# Main.net
KiCad netlist of a schematic drawn in Altium Designer
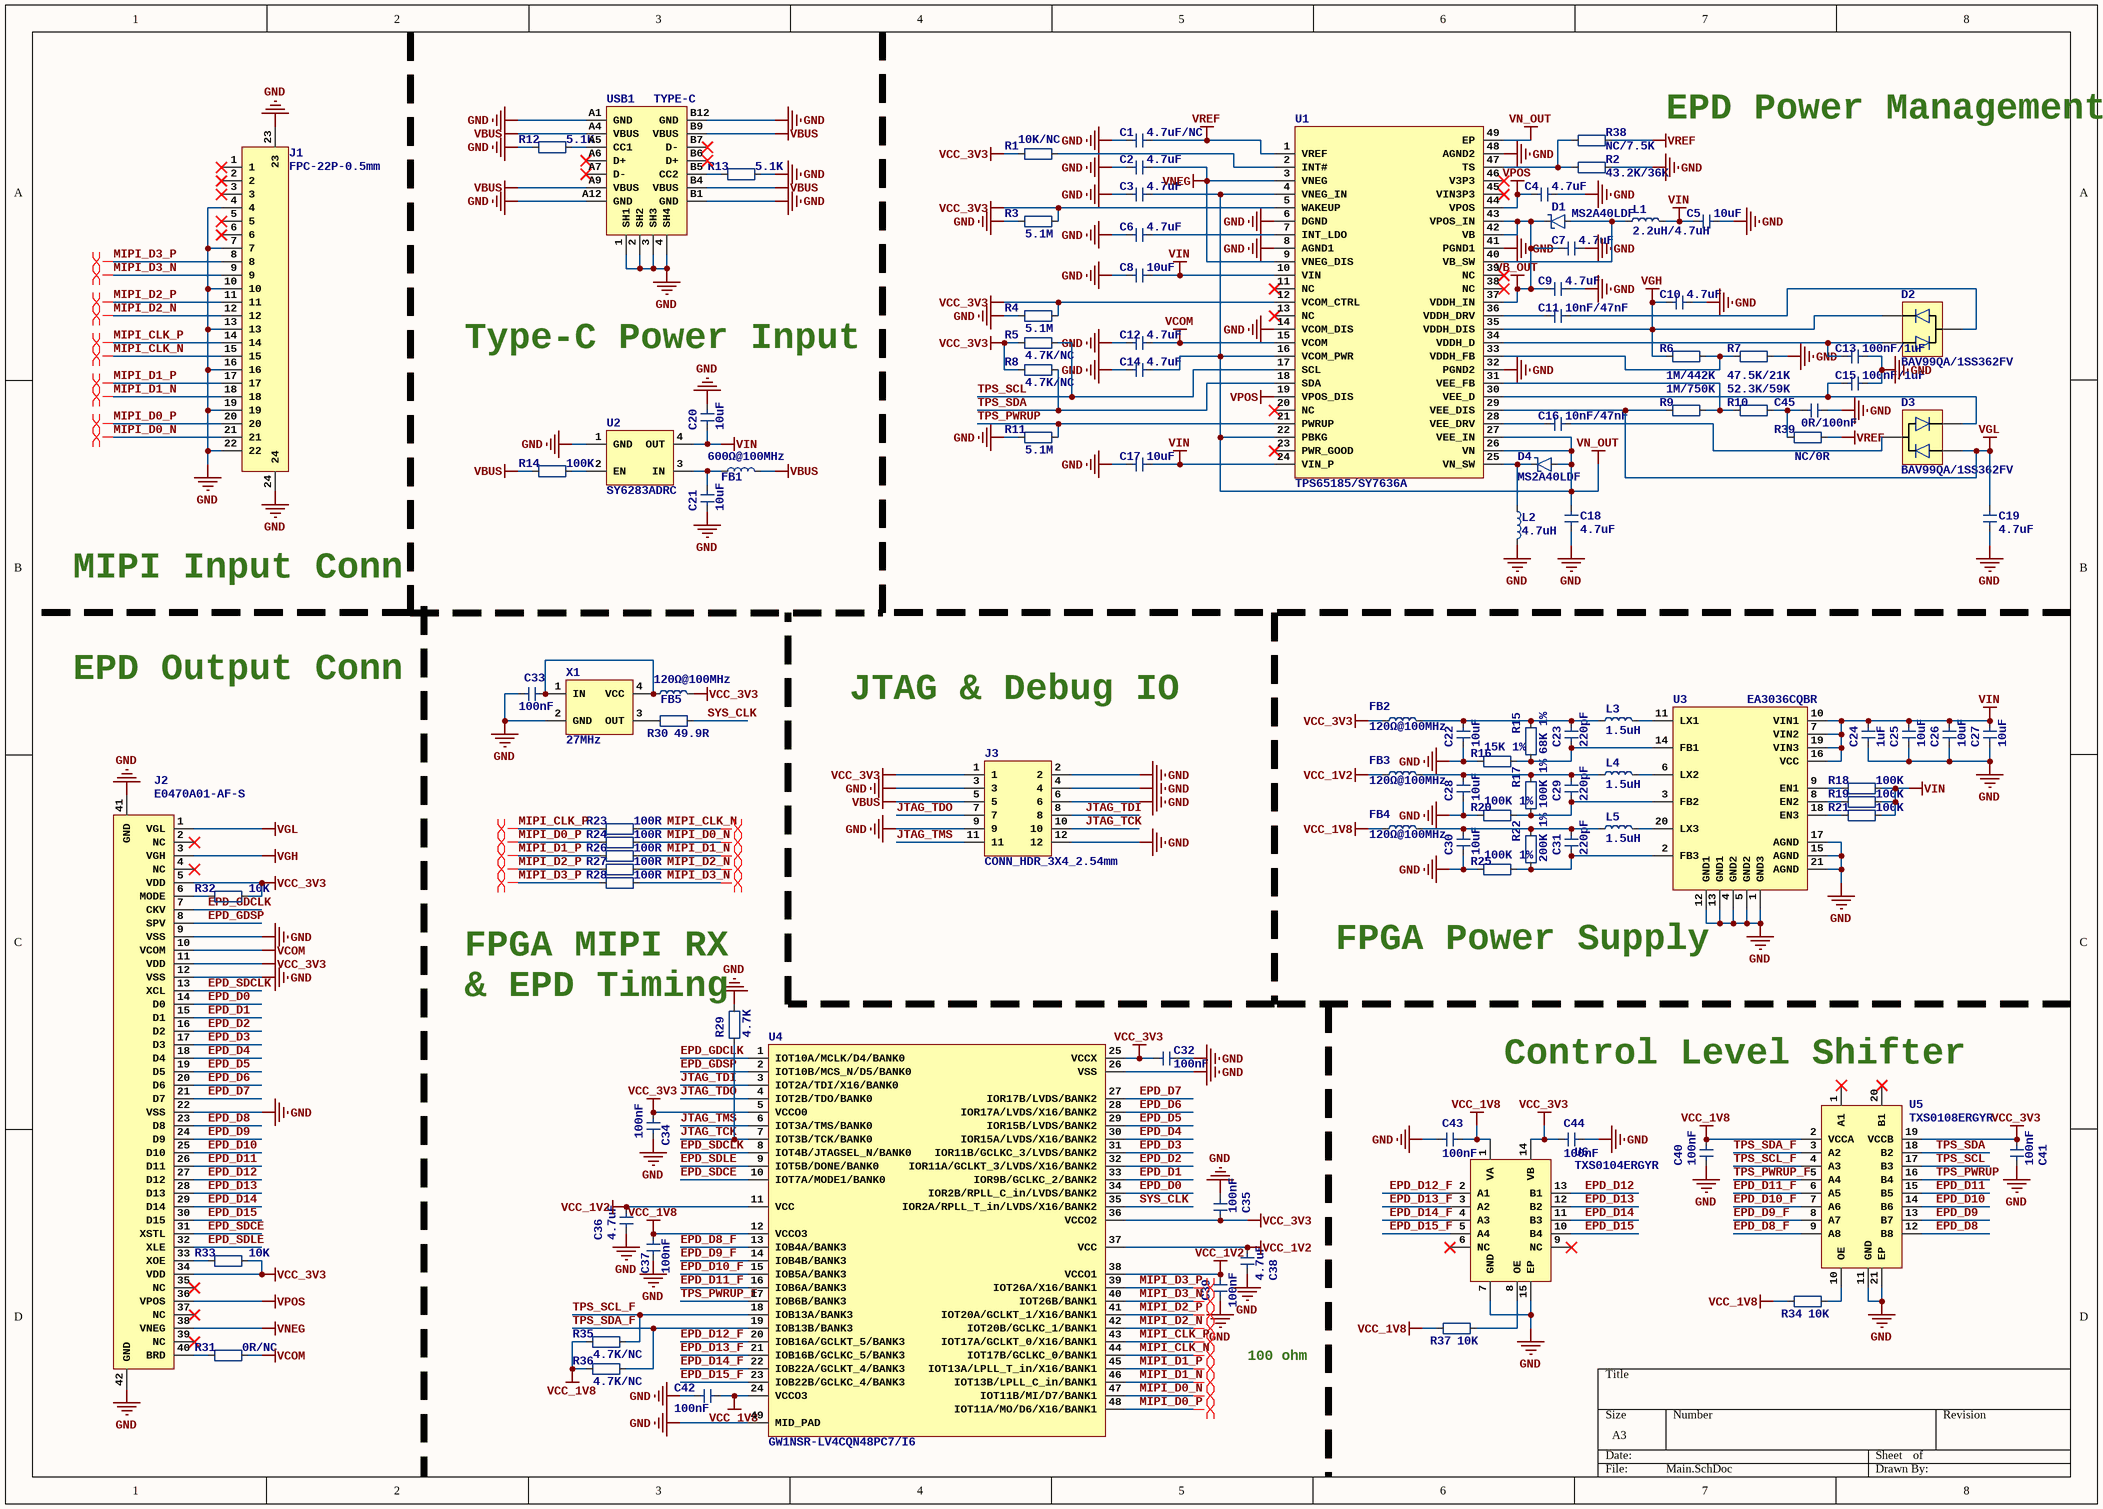
[diagram p0: Main.SchDoc]

(export (version "E")
  (design (tool "Eeschema 10.0.6"))
  (components
    (comp (ref "C1")
      (value "4.7uF/NC")
      (footprint "Capacitor-0402")
      (description "CL05A475MO5NUNC")
      (libsource (lib "mLib") (part "Capacitor-0402"))
    )
    (comp (ref "C2")
      (value "4.7uF")
      (footprint "Capacitor-0805")
      (description "CL21A475KBQNNNE")
      (libsource (lib "mLib") (part "Capacitor-0805"))
    )
    (comp (ref "C3")
      (value "4.7uF")
      (footprint "Capacitor-0805")
      (description "CL21A475KBQNNNE")
      (libsource (lib "mLib") (part "Capacitor-0805"))
    )
    (comp (ref "C4")
      (value "4.7uF")
      (footprint "Capacitor-0805")
      (description "CL21A475KBQNNNE")
      (libsource (lib "mLib") (part "Capacitor-0805"))
    )
    (comp (ref "C5")
      (value "10uF")
      (footprint "Capacitor-0603")
      (description "CL10A106KP8NNNC")
      (libsource (lib "mLib") (part "Capacitor-0603"))
    )
    (comp (ref "C6")
      (value "4.7uF")
      (footprint "Capacitor-0402")
      (description "CL05A475MO5NUNC")
      (libsource (lib "mLib") (part "Capacitor-0402"))
    )
    (comp (ref "C7")
      (value "4.7uF")
      (footprint "Capacitor-0805")
      (description "CL21A475KBQNNNE")
      (libsource (lib "mLib") (part "Capacitor-0805"))
    )
    (comp (ref "C8")
      (value "10uF")
      (footprint "Capacitor-0603")
      (description "CL10A106KP8NNNC")
      (libsource (lib "mLib") (part "Capacitor-0603"))
    )
    (comp (ref "C9")
      (value "4.7uF")
      (footprint "Capacitor-0805")
      (description "CL21A475KBQNNNE")
      (libsource (lib "mLib") (part "Capacitor-0805"))
    )
    (comp (ref "C10")
      (value "4.7uF")
      (footprint "Capacitor-0805")
      (description "CL21A475KBQNNNE")
      (libsource (lib "mLib") (part "Capacitor-0805"))
    )
    (comp (ref "C11")
      (value "10nF/47nF")
      (footprint "Capacitor-0402")
      (description "CL05B103KB5NNNC/CC0402KRX7R9BB473")
      (libsource (lib "mLib") (part "Capacitor-0402"))
    )
    (comp (ref "C12")
      (value "4.7uF")
      (footprint "Capacitor-0402")
      (description "CL05A475MO5NUNC")
      (libsource (lib "mLib") (part "Capacitor-0402"))
    )
    (comp (ref "C13")
      (value "100nF/1uF")
      (footprint "Capacitor-0402")
      (description "0402B104K500NT/HGC0402R5105K500NTEJ")
      (libsource (lib "mLib") (part "Capacitor-0402"))
    )
    (comp (ref "C14")
      (value "4.7uF")
      (footprint "Capacitor-0805")
      (description "CL21A475KBQNNNE")
      (libsource (lib "mLib") (part "Capacitor-0805"))
    )
    (comp (ref "C15")
      (value "100nF/1uF")
      (footprint "Capacitor-0402")
      (description "0402B104K500NT/HGC0402R5105K500NTEJ")
      (libsource (lib "mLib") (part "Capacitor-0402"))
    )
    (comp (ref "C16")
      (value "10nF/47nF")
      (footprint "Capacitor-0402")
      (description "CL05B103KB5NNNC/CC0402KRX7R9BB473")
      (libsource (lib "mLib") (part "Capacitor-0402"))
    )
    (comp (ref "C17")
      (value "10uF")
      (footprint "Capacitor-0603")
      (description "CL10A106KP8NNNC")
      (libsource (lib "mLib") (part "Capacitor-0603"))
    )
    (comp (ref "C18")
      (value "4.7uF")
      (footprint "Capacitor-0805")
      (description "CL21A475KBQNNNE")
      (libsource (lib "mLib") (part "Capacitor-0805"))
    )
    (comp (ref "C19")
      (value "4.7uF")
      (footprint "Capacitor-0805")
      (description "CL21A475KBQNNNE")
      (libsource (lib "mLib") (part "Capacitor-0805"))
    )
    (comp (ref "C20")
      (value "10uF")
      (footprint "Capacitor-0402")
      (description "HGC0402R5106M100NTEJ")
      (libsource (lib "mLib") (part "Capacitor-0402"))
    )
    (comp (ref "C21")
      (value "10uF")
      (footprint "Capacitor-0402")
      (description "HGC0402R5106M100NTEJ")
      (libsource (lib "mLib") (part "Capacitor-0402"))
    )
    (comp (ref "C22")
      (value "10uF")
      (footprint "Capacitor-0402")
      (description "HGC0402R5106M100NTEJ")
      (libsource (lib "mLib") (part "Capacitor-0402"))
    )
    (comp (ref "C23")
      (value "220pF")
      (footprint "Capacitor-0402")
      (description "CL05C221JB5NNNC")
      (libsource (lib "mLib") (part "Capacitor-0402"))
    )
    (comp (ref "C24")
      (value "1uF")
      (footprint "Capacitor-0402")
      (description "HGC0402R5105K500NTEJ")
      (libsource (lib "mLib") (part "Capacitor-0402"))
    )
    (comp (ref "C25")
      (value "10uF")
      (footprint "Capacitor-0402")
      (description "HGC0402R5106M100NTEJ")
      (libsource (lib "mLib") (part "Capacitor-0402"))
    )
    (comp (ref "C26")
      (value "10uF")
      (footprint "Capacitor-0402")
      (description "HGC0402R5106M100NTEJ")
      (libsource (lib "mLib") (part "Capacitor-0402"))
    )
    (comp (ref "C27")
      (value "10uF")
      (footprint "Capacitor-0402")
      (description "HGC0402R5106M100NTEJ")
      (libsource (lib "mLib") (part "Capacitor-0402"))
    )
    (comp (ref "C28")
      (value "10uF")
      (footprint "Capacitor-0402")
      (description "HGC0402R5106M100NTEJ")
      (libsource (lib "mLib") (part "Capacitor-0402"))
    )
    (comp (ref "C29")
      (value "220pF")
      (footprint "Capacitor-0402")
      (description "CL05C221JB5NNNC")
      (libsource (lib "mLib") (part "Capacitor-0402"))
    )
    (comp (ref "C30")
      (value "10uF")
      (footprint "Capacitor-0402")
      (description "HGC0402R5106M100NTEJ")
      (libsource (lib "mLib") (part "Capacitor-0402"))
    )
    (comp (ref "C31")
      (value "220pF")
      (footprint "Capacitor-0402")
      (description "CL05C221JB5NNNC")
      (libsource (lib "mLib") (part "Capacitor-0402"))
    )
    (comp (ref "C32")
      (value "100nF")
      (footprint "Capacitor-0402")
      (description "100nF/X5R/25V")
      (libsource (lib "mLib") (part "Capacitor-0402"))
    )
    (comp (ref "C33")
      (value "100nF")
      (footprint "Capacitor-0402")
      (description "100nF/X5R/25V")
      (libsource (lib "mLib") (part "Capacitor-0402"))
    )
    (comp (ref "C34")
      (value "100nF")
      (footprint "Capacitor-0402")
      (description "100nF/X5R/25V")
      (libsource (lib "mLib") (part "Capacitor-0402"))
    )
    (comp (ref "C35")
      (value "100nF")
      (footprint "Capacitor-0402")
      (description "100nF/X5R/25V")
      (libsource (lib "mLib") (part "Capacitor-0402"))
    )
    (comp (ref "C36")
      (value "4.7uF")
      (footprint "Capacitor-0402")
      (description "4.7uF/X5R/10V")
      (libsource (lib "mLib") (part "Capacitor-0402"))
    )
    (comp (ref "C37")
      (value "100nF")
      (footprint "Capacitor-0402")
      (description "100nF/X5R/25V")
      (libsource (lib "mLib") (part "Capacitor-0402"))
    )
    (comp (ref "C38")
      (value "4.7uF")
      (footprint "Capacitor-0402")
      (description "4.7uF/X5R/10V")
      (libsource (lib "mLib") (part "Capacitor-0402"))
    )
    (comp (ref "C39")
      (value "100nF")
      (footprint "Capacitor-0402")
      (description "100nF/X5R/25V")
      (libsource (lib "mLib") (part "Capacitor-0402"))
    )
    (comp (ref "C40")
      (value "100nF")
      (footprint "Capacitor-0402")
      (description "100nF/X5R/25V")
      (libsource (lib "mLib") (part "Capacitor-0402"))
    )
    (comp (ref "C41")
      (value "100nF")
      (footprint "Capacitor-0402")
      (description "100nF/X5R/25V")
      (libsource (lib "mLib") (part "Capacitor-0402"))
    )
    (comp (ref "C42")
      (value "100nF")
      (footprint "Capacitor-0402")
      (description "100nF/X5R/25V")
      (libsource (lib "mLib") (part "Capacitor-0402"))
    )
    (comp (ref "C43")
      (value "100nF")
      (footprint "Capacitor-0402")
      (description "100nF/X5R/25V")
      (libsource (lib "mLib") (part "Capacitor-0402"))
    )
    (comp (ref "C44")
      (value "100nF")
      (footprint "Capacitor-0402")
      (description "100nF/X5R/25V")
      (libsource (lib "mLib") (part "Capacitor-0402"))
    )
    (comp (ref "C45")
      (value "0R/100nF")
      (footprint "Capacitor-0402")
      (description "CL05B104KB5NNNC")
      (libsource (lib "mLib") (part "Capacitor-0402"))
    )
    (comp (ref "D1")
      (value "MS2A40LDF")
      (footprint "MS2A40LDF-DFN-2_1.6x1.0mm")
      (description "Schottky Diode-DFN-1610-2")
      (libsource (lib "mLib") (part "MS2A40LDF"))
    )
    (comp (ref "D2")
      (value "BAV99QA/1SS362FV")
      (footprint "BAV99QA-DFN-3_1.1x1.0mm")
      (libsource (lib "") (part "BAV99QA_1"))
    )
    (comp (ref "D3")
      (value "BAV99QA/1SS362FV")
      (footprint "BAV99QA-DFN-3_1.1x1.0mm")
      (libsource (lib "mLib") (part "BAV99QA"))
    )
    (comp (ref "D4")
      (value "MS2A40LDF")
      (footprint "MS2A40LDF-DFN-2_1.6x1.0mm")
      (description "Schottky Diode-DFN-1610-2")
      (libsource (lib "mLib") (part "MS2A40LDF"))
    )
    (comp (ref "FB1")
      (value "600Ω@100MHz")
      (footprint "Ferrite Bead-0603")
      (description "UPZ1608U601-1R3TF")
      (libsource (lib "mLib") (part "Ferrite Bead-0603"))
    )
    (comp (ref "FB2")
      (value "120Ω@100MHz")
      (footprint "Ferrite Bead-0402")
      (description "UPZ1005D121-1R3TF")
      (libsource (lib "mLib") (part "Ferrite Bead-0402"))
    )
    (comp (ref "FB3")
      (value "120Ω@100MHz")
      (footprint "Ferrite Bead-0402")
      (description "UPZ1005D121-1R3TF")
      (libsource (lib "mLib") (part "Ferrite Bead-0402"))
    )
    (comp (ref "FB4")
      (value "120Ω@100MHz")
      (footprint "Ferrite Bead-0402")
      (description "UPZ1005D121-1R3TF")
      (libsource (lib "mLib") (part "Ferrite Bead-0402"))
    )
    (comp (ref "FB5")
      (value "120Ω@100MHz")
      (footprint "Ferrite Bead-0402")
      (description "UPZ1005D121-1R3TF")
      (libsource (lib "mLib") (part "Ferrite Bead-0402"))
    )
    (comp (ref "J1")
      (value "FPC-22P-0.5mm")
      (footprint "HC-FPC-05-10-22RLTAG")
      (description "HC-FPC-05-10-22RLTAG")
      (libsource (lib "mLib") (part "FPC-22P-0.5mm"))
    )
    (comp (ref "J2")
      (value "E0470A01-AF-S")
      (footprint "E0470A01-AF-S")
      (description "AFC01-S40FCA-00")
      (libsource (lib "mLib") (part "E0470A01-AF-S"))
    )
    (comp (ref "J3")
      (value "CONN_HDR_3X4_2.54mm")
      (footprint "CONN_HDR_3X4_2.54mm")
      (libsource (lib "mLib") (part "CONN_HDR_3X4_2.54mm"))
    )
    (comp (ref "L1")
      (value "2.2uH/4.7uH")
      (footprint "Inductor-2016")
      (description "FTC201612S2R2MBCA/FTC201610S4R7MBCA")
      (libsource (lib "mLib") (part "Inductor-2016"))
    )
    (comp (ref "L2")
      (value "4.7uH")
      (footprint "Inductor-2016")
      (description "FTC201610S4R7MBCA")
      (libsource (lib "mLib") (part "Inductor-2016"))
    )
    (comp (ref "L3")
      (value "1.5uH")
      (footprint "Inductor-2016")
      (description "FTC201610S1R5MBCA")
      (libsource (lib "mLib") (part "Inductor-2016"))
    )
    (comp (ref "L4")
      (value "1.5uH")
      (footprint "Inductor-2016")
      (description "FTC201610S1R5MBCA")
      (libsource (lib "mLib") (part "Inductor-2016"))
    )
    (comp (ref "L5")
      (value "1.5uH")
      (footprint "Inductor-2016")
      (description "FTC201610S1R5MBCA")
      (libsource (lib "mLib") (part "Inductor-2016"))
    )
    (comp (ref "R1")
      (value "10K/NC")
      (footprint "Resistor-0402")
      (description "Resistor-0402")
      (libsource (lib "mLib") (part "Resistor-0402"))
    )
    (comp (ref "R2")
      (value "43.2K/36K")
      (footprint "Resistor-0402")
      (description "Resistor-0402")
      (libsource (lib "mLib") (part "Resistor-0402"))
    )
    (comp (ref "R3")
      (value "5.1M")
      (footprint "Resistor-0402")
      (description "Resistor-0402")
      (libsource (lib "mLib") (part "Resistor-0402"))
    )
    (comp (ref "R4")
      (value "5.1M")
      (footprint "Resistor-0402")
      (description "Resistor-0402")
      (libsource (lib "mLib") (part "Resistor-0402"))
    )
    (comp (ref "R5")
      (value "4.7K/NC")
      (footprint "Resistor-0402")
      (description "Resistor-0402")
      (libsource (lib "mLib") (part "Resistor-0402"))
    )
    (comp (ref "R6")
      (value "1M/442K")
      (footprint "Resistor-0402")
      (description "Resistor-0402")
      (libsource (lib "mLib") (part "Resistor-0402"))
    )
    (comp (ref "R7")
      (value "47.5K/21K")
      (footprint "Resistor-0402")
      (description "Resistor-0402")
      (libsource (lib "mLib") (part "Resistor-0402"))
    )
    (comp (ref "R8")
      (value "4.7K/NC")
      (footprint "Resistor-0402")
      (description "Resistor-0402")
      (libsource (lib "mLib") (part "Resistor-0402"))
    )
    (comp (ref "R9")
      (value "1M/750K")
      (footprint "Resistor-0402")
      (description "Resistor-0402")
      (libsource (lib "mLib") (part "Resistor-0402"))
    )
    (comp (ref "R10")
      (value "52.3K/59K")
      (footprint "Resistor-0402")
      (description "Resistor-0402")
      (libsource (lib "mLib") (part "Resistor-0402"))
    )
    (comp (ref "R11")
      (value "5.1M")
      (footprint "Resistor-0402")
      (description "Resistor-0402")
      (libsource (lib "mLib") (part "Resistor-0402"))
    )
    (comp (ref "R12")
      (value "5.1K")
      (footprint "Resistor-0402")
      (description "Resistor-0402")
      (libsource (lib "mLib") (part "Resistor-0402"))
    )
    (comp (ref "R13")
      (value "5.1K")
      (footprint "Resistor-0402")
      (description "Resistor-0402")
      (libsource (lib "mLib") (part "Resistor-0402"))
    )
    (comp (ref "R14")
      (value "100K")
      (footprint "Resistor-0402")
      (description "Resistor-0402")
      (libsource (lib "mLib") (part "Resistor-0402"))
    )
    (comp (ref "R15")
      (value "68K 1%")
      (footprint "Resistor-0402")
      (description "Resistor-0402")
      (libsource (lib "mLib") (part "Resistor-0402"))
    )
    (comp (ref "R16")
      (value "15K 1%")
      (footprint "Resistor-0402")
      (description "Resistor-0402")
      (libsource (lib "mLib") (part "Resistor-0402"))
    )
    (comp (ref "R17")
      (value "100K 1%")
      (footprint "Resistor-0402")
      (description "Resistor-0402")
      (libsource (lib "mLib") (part "Resistor-0402"))
    )
    (comp (ref "R18")
      (value "100K")
      (footprint "Resistor-0402")
      (description "Resistor-0402")
      (libsource (lib "mLib") (part "Resistor-0402"))
    )
    (comp (ref "R19")
      (value "100K")
      (footprint "Resistor-0402")
      (description "Resistor-0402")
      (libsource (lib "mLib") (part "Resistor-0402"))
    )
    (comp (ref "R20")
      (value "100K 1%")
      (footprint "Resistor-0402")
      (description "Resistor-0402")
      (libsource (lib "mLib") (part "Resistor-0402"))
    )
    (comp (ref "R21")
      (value "100K")
      (footprint "Resistor-0402")
      (description "Resistor-0402")
      (libsource (lib "mLib") (part "Resistor-0402"))
    )
    (comp (ref "R22")
      (value "200K 1%")
      (footprint "Resistor-0402")
      (description "Resistor-0402")
      (libsource (lib "mLib") (part "Resistor-0402"))
    )
    (comp (ref "R23")
      (value "100R")
      (footprint "Resistor-0402")
      (description "Resistor-0402")
      (libsource (lib "mLib") (part "Resistor-0402"))
    )
    (comp (ref "R24")
      (value "100R")
      (footprint "Resistor-0402")
      (description "Resistor-0402")
      (libsource (lib "mLib") (part "Resistor-0402"))
    )
    (comp (ref "R25")
      (value "100K 1%")
      (footprint "Resistor-0402")
      (description "Resistor-0402")
      (libsource (lib "mLib") (part "Resistor-0402"))
    )
    (comp (ref "R26")
      (value "100R")
      (footprint "Resistor-0402")
      (description "Resistor-0402")
      (libsource (lib "mLib") (part "Resistor-0402"))
    )
    (comp (ref "R27")
      (value "100R")
      (footprint "Resistor-0402")
      (description "Resistor-0402")
      (libsource (lib "mLib") (part "Resistor-0402"))
    )
    (comp (ref "R28")
      (value "100R")
      (footprint "Resistor-0402")
      (description "Resistor-0402")
      (libsource (lib "mLib") (part "Resistor-0402"))
    )
    (comp (ref "R29")
      (value "4.7K")
      (footprint "Resistor-0402")
      (description "Resistor-0402")
      (libsource (lib "mLib") (part "Resistor-0402"))
    )
    (comp (ref "R30")
      (value "49.9R")
      (footprint "Resistor-0402")
      (description "Resistor-0402")
      (libsource (lib "mLib") (part "Resistor-0402"))
    )
    (comp (ref "R31")
      (value "0R/NC")
      (footprint "Resistor-0402")
      (description "Resistor-0402")
      (libsource (lib "mLib") (part "Resistor-0402"))
    )
    (comp (ref "R32")
      (value "10K")
      (footprint "Resistor-0402")
      (description "Resistor-0402")
      (libsource (lib "mLib") (part "Resistor-0402"))
    )
    (comp (ref "R33")
      (value "10K")
      (footprint "Resistor-0402")
      (description "Resistor-0402")
      (libsource (lib "mLib") (part "Resistor-0402"))
    )
    (comp (ref "R34")
      (value "10K")
      (footprint "Resistor-0402")
      (description "Resistor-0402")
      (libsource (lib "mLib") (part "Resistor-0402"))
    )
    (comp (ref "R35")
      (value "4.7K/NC")
      (footprint "Resistor-0402")
      (description "Resistor-0402")
      (libsource (lib "mLib") (part "Resistor-0402"))
    )
    (comp (ref "R36")
      (value "4.7K/NC")
      (footprint "Resistor-0402")
      (description "Resistor-0402")
      (libsource (lib "mLib") (part "Resistor-0402"))
    )
    (comp (ref "R37")
      (value "10K")
      (footprint "Resistor-0402")
      (description "Resistor-0402")
      (libsource (lib "mLib") (part "Resistor-0402"))
    )
    (comp (ref "R38")
      (value "NC/7.5K")
      (footprint "Resistor-0402")
      (description "Resistor-0402")
      (libsource (lib "mLib") (part "Resistor-0402"))
    )
    (comp (ref "R39")
      (value "NC/0R")
      (footprint "Resistor-0402")
      (description "Resistor-0402")
      (libsource (lib "mLib") (part "Resistor-0402"))
    )
    (comp (ref "U1")
      (value "TPS65185/SY7636A")
      (footprint "TPS65185-VQFN-48_6x6mm")
      (libsource (lib "mLib") (part "TPS65185"))
    )
    (comp (ref "U2")
      (value "SY6283ADRC")
      (footprint "SY6283ADRC-dfn-4_1.2x1.6mm")
      (libsource (lib "mLib") (part "SY6283ADRC"))
    )
    (comp (ref "U3")
      (value "EA3036CQBR")
      (footprint "EA3036-QFN-20")
      (libsource (lib "mLib") (part "EA3036CQBR"))
    )
    (comp (ref "U4")
      (value "GW1NSR-LV4CQN48PC7/I6")
      (footprint "GW1NSR-LV4CQN48P-QFN-48_6X6")
      (libsource (lib "mLib") (part "GW1NSR-LV4CQN48P"))
    )
    (comp (ref "U5")
      (value "TXS0108ERGYR")
      (footprint "TXS0108E-VQFN-20-3.5x4.5mm")
      (libsource (lib "mLib") (part "TXS0108E"))
    )
    (comp (ref "U6")
      (value "TXS0104ERGYR")
      (footprint "TXS0104E-VQFN-14-3.5x3.5mm")
      (libsource (lib "mLib") (part "TXS0104E"))
    )
    (comp (ref "USB1")
      (value "TYPE-C")
      (footprint "TYPE-C-16P")
      (description "GT-USB-7010ASV")
      (libsource (lib "mLib") (part "TYPE-C"))
    )
    (comp (ref "X1")
      (value "27MHz")
      (footprint "Oscillator-2016")
      (description "OC7EL89CJO-113YLC-27M")
      (libsource (lib "mLib") (part "Oscillator_Source-2016"))
    )
  )
  (nets
    (net (code "1") (name "/EPD_D0") (class "Default")
      (node (ref "J2") (pin "14") (pinfunction "D0_14") (pintype "passive"))
      (node (ref "U4") (pin "34") (pinfunction "IOR2B/RPLL_C_in/LVDS/BANK2_34") (pintype "passive"))
    )
    (net (code "2") (name "/EPD_D1") (class "Default")
      (node (ref "J2") (pin "15") (pinfunction "D1_15") (pintype "passive"))
      (node (ref "U4") (pin "33") (pinfunction "IOR9B/GCLKC_2/BANK2_33") (pintype "passive"))
    )
    (net (code "3") (name "/EPD_D2") (class "Default")
      (node (ref "J2") (pin "16") (pinfunction "D2_16") (pintype "passive"))
      (node (ref "U4") (pin "32") (pinfunction "IOR11A/GCLKT_3/LVDS/X16/BANK2_32") (pintype "passive"))
    )
    (net (code "4") (name "/EPD_D3") (class "Default")
      (node (ref "J2") (pin "17") (pinfunction "D3_17") (pintype "passive"))
      (node (ref "U4") (pin "31") (pinfunction "IOR11B/GCLKC_3/LVDS/BANK2_31") (pintype "passive"))
    )
    (net (code "5") (name "/EPD_D4") (class "Default")
      (node (ref "J2") (pin "18") (pinfunction "D4_18") (pintype "passive"))
      (node (ref "U4") (pin "30") (pinfunction "IOR15A/LVDS/X16/BANK2_30") (pintype "passive"))
    )
    (net (code "6") (name "/EPD_D5") (class "Default")
      (node (ref "J2") (pin "19") (pinfunction "D5_19") (pintype "passive"))
      (node (ref "U4") (pin "29") (pinfunction "IOR15B/LVDS/BANK2_29") (pintype "passive"))
    )
    (net (code "7") (name "/EPD_D6") (class "Default")
      (node (ref "J2") (pin "20") (pinfunction "D6_20") (pintype "passive"))
      (node (ref "U4") (pin "28") (pinfunction "IOR17A/LVDS/X16/BANK2_28") (pintype "passive"))
    )
    (net (code "8") (name "/EPD_D7") (class "Default")
      (node (ref "J2") (pin "21") (pinfunction "D7_21") (pintype "passive"))
      (node (ref "U4") (pin "27") (pinfunction "IOR17B/LVDS/BANK2_27") (pintype "passive"))
    )
    (net (code "9") (name "/EPD_D8") (class "Default")
      (node (ref "J2") (pin "23") (pinfunction "D8_23") (pintype "passive"))
      (node (ref "U5") (pin "12") (pinfunction "B8_12") (pintype "passive"))
    )
    (net (code "10") (name "/EPD_D8_F") (class "Default")
      (node (ref "U4") (pin "13") (pinfunction "IOB4A/BANK3_13") (pintype "passive"))
      (node (ref "U5") (pin "9") (pinfunction "A8_9") (pintype "passive"))
    )
    (net (code "11") (name "/EPD_D9") (class "Default")
      (node (ref "J2") (pin "24") (pinfunction "D9_24") (pintype "passive"))
      (node (ref "U5") (pin "13") (pinfunction "B7_13") (pintype "passive"))
    )
    (net (code "12") (name "/EPD_D9_F") (class "Default")
      (node (ref "U4") (pin "14") (pinfunction "IOB4B/BANK3_14") (pintype "passive"))
      (node (ref "U5") (pin "8") (pinfunction "A7_8") (pintype "passive"))
    )
    (net (code "13") (name "/EPD_D10") (class "Default")
      (node (ref "J2") (pin "25") (pinfunction "D10_25") (pintype "passive"))
      (node (ref "U5") (pin "14") (pinfunction "B6_14") (pintype "passive"))
    )
    (net (code "14") (name "/EPD_D10_F") (class "Default")
      (node (ref "U4") (pin "15") (pinfunction "IOB5A/BANK3_15") (pintype "passive"))
      (node (ref "U5") (pin "7") (pinfunction "A6_7") (pintype "passive"))
    )
    (net (code "15") (name "/EPD_D11") (class "Default")
      (node (ref "J2") (pin "26") (pinfunction "D11_26") (pintype "passive"))
      (node (ref "U5") (pin "15") (pinfunction "B5_15") (pintype "passive"))
    )
    (net (code "16") (name "/EPD_D11_F") (class "Default")
      (node (ref "U4") (pin "16") (pinfunction "IOB6A/BANK3_16") (pintype "passive"))
      (node (ref "U5") (pin "6") (pinfunction "A5_6") (pintype "passive"))
    )
    (net (code "17") (name "/EPD_D12") (class "Default")
      (node (ref "J2") (pin "27") (pinfunction "D12_27") (pintype "passive"))
      (node (ref "U6") (pin "13") (pinfunction "B1_13") (pintype "passive"))
    )
    (net (code "18") (name "/EPD_D12_F") (class "Default")
      (node (ref "U4") (pin "20") (pinfunction "IOB16A/GCLKT_5/BANK3_20") (pintype "passive"))
      (node (ref "U6") (pin "2") (pinfunction "A1_2") (pintype "passive"))
    )
    (net (code "19") (name "/EPD_D13") (class "Default")
      (node (ref "J2") (pin "28") (pinfunction "D13_28") (pintype "passive"))
      (node (ref "U6") (pin "12") (pinfunction "B2_12") (pintype "passive"))
    )
    (net (code "20") (name "/EPD_D13_F") (class "Default")
      (node (ref "U4") (pin "21") (pinfunction "IOB16B/GCLKC_5/BANK3_21") (pintype "passive"))
      (node (ref "U6") (pin "3") (pinfunction "A2_3") (pintype "passive"))
    )
    (net (code "21") (name "/EPD_D14") (class "Default")
      (node (ref "J2") (pin "29") (pinfunction "D14_29") (pintype "passive"))
      (node (ref "U6") (pin "11") (pinfunction "B3_11") (pintype "passive"))
    )
    (net (code "22") (name "/EPD_D14_F") (class "Default")
      (node (ref "U4") (pin "22") (pinfunction "IOB22A/GCLKT_4/BANK3_22") (pintype "passive"))
      (node (ref "U6") (pin "4") (pinfunction "A3_4") (pintype "passive"))
    )
    (net (code "23") (name "/EPD_D15") (class "Default")
      (node (ref "J2") (pin "30") (pinfunction "D15_30") (pintype "passive"))
      (node (ref "U6") (pin "10") (pinfunction "B4_10") (pintype "passive"))
    )
    (net (code "24") (name "/EPD_D15_F") (class "Default")
      (node (ref "U4") (pin "23") (pinfunction "IOB22B/GCLKC_4/BANK3_23") (pintype "passive"))
      (node (ref "U6") (pin "5") (pinfunction "A4_5") (pintype "passive"))
    )
    (net (code "25") (name "/EPD_GDCLK") (class "Default")
      (node (ref "J2") (pin "7") (pinfunction "CKV_7") (pintype "passive"))
      (node (ref "U4") (pin "1") (pinfunction "IOT10A/MCLK/D4/BANK0_1") (pintype "passive"))
    )
    (net (code "26") (name "/EPD_GDSP") (class "Default")
      (node (ref "J2") (pin "8") (pinfunction "SPV_8") (pintype "passive"))
      (node (ref "U4") (pin "2") (pinfunction "IOT10B/MCS_N/D5/BANK0_2") (pintype "passive"))
    )
    (net (code "27") (name "/EPD_SDCE") (class "Default")
      (node (ref "J2") (pin "31") (pinfunction "XSTL_31") (pintype "passive"))
      (node (ref "U4") (pin "10") (pinfunction "IOT7A/MODE1/BANK0_10") (pintype "passive"))
    )
    (net (code "28") (name "/EPD_SDCLK") (class "Default")
      (node (ref "J2") (pin "13") (pinfunction "XCL_13") (pintype "passive"))
      (node (ref "U4") (pin "8") (pinfunction "IOT4B/JTAGSEL_N/BANK0_8") (pintype "passive"))
    )
    (net (code "29") (name "/EPD_SDLE") (class "Default")
      (node (ref "J2") (pin "32") (pinfunction "XLE_32") (pintype "passive"))
      (node (ref "U4") (pin "9") (pinfunction "IOT5B/DONE/BANK0_9") (pintype "passive"))
    )
    (net (code "30") (name "/JTAG_TCK") (class "Default")
      (node (ref "J3") (pin "10") (pinfunction "10_10") (pintype "passive"))
      (node (ref "R29") (pin "1") (pinfunction "1_1") (pintype "passive"))
      (node (ref "U4") (pin "7") (pinfunction "IOT3B/TCK/BANK0_7") (pintype "passive"))
    )
    (net (code "31") (name "/JTAG_TDI") (class "Default")
      (node (ref "J3") (pin "8") (pinfunction "8_8") (pintype "passive"))
      (node (ref "U4") (pin "3") (pinfunction "IOT2A/TDI/X16/BANK0_3") (pintype "passive"))
    )
    (net (code "32") (name "/JTAG_TDO") (class "Default")
      (node (ref "J3") (pin "7") (pinfunction "7_7") (pintype "passive"))
      (node (ref "U4") (pin "4") (pinfunction "IOT2B/TDO/BANK0_4") (pintype "passive"))
    )
    (net (code "33") (name "/JTAG_TMS") (class "Default")
      (node (ref "J3") (pin "11") (pinfunction "11_11") (pintype "passive"))
      (node (ref "U4") (pin "6") (pinfunction "IOT3A/TMS/BANK0_6") (pintype "passive"))
    )
    (net (code "34") (name "/MIPI_CLK_N") (class "Default")
      (node (ref "J1") (pin "15") (pinfunction "15_15") (pintype "passive"))
      (node (ref "R23") (pin "1") (pinfunction "1_1") (pintype "passive"))
      (node (ref "U4") (pin "44") (pinfunction "IOT17B/GCLKC_0/BANK1_44") (pintype "passive"))
    )
    (net (code "35") (name "/MIPI_CLK_P") (class "Default")
      (node (ref "J1") (pin "14") (pinfunction "14_14") (pintype "passive"))
      (node (ref "R23") (pin "2") (pinfunction "2_2") (pintype "passive"))
      (node (ref "U4") (pin "43") (pinfunction "IOT17A/GCLKT_0/X16/BANK1_43") (pintype "passive"))
    )
    (net (code "36") (name "/MIPI_D0_N") (class "Default")
      (node (ref "J1") (pin "21") (pinfunction "21_21") (pintype "passive"))
      (node (ref "R24") (pin "1") (pinfunction "1_1") (pintype "passive"))
      (node (ref "U4") (pin "47") (pinfunction "IOT11B/MI/D7/BANK1_47") (pintype "passive"))
    )
    (net (code "37") (name "/MIPI_D0_P") (class "Default")
      (node (ref "J1") (pin "20") (pinfunction "20_20") (pintype "passive"))
      (node (ref "R24") (pin "2") (pinfunction "2_2") (pintype "passive"))
      (node (ref "U4") (pin "48") (pinfunction "IOT11A/MO/D6/X16/BANK1_48") (pintype "passive"))
    )
    (net (code "38") (name "/MIPI_D1_N") (class "Default")
      (node (ref "J1") (pin "18") (pinfunction "18_18") (pintype "passive"))
      (node (ref "R26") (pin "1") (pinfunction "1_1") (pintype "passive"))
      (node (ref "U4") (pin "46") (pinfunction "IOT13B/LPLL_C_in/BANK1_46") (pintype "passive"))
    )
    (net (code "39") (name "/MIPI_D1_P") (class "Default")
      (node (ref "J1") (pin "17") (pinfunction "17_17") (pintype "passive"))
      (node (ref "R26") (pin "2") (pinfunction "2_2") (pintype "passive"))
      (node (ref "U4") (pin "45") (pinfunction "IOT13A/LPLL_T_in/X16/BANK1_45") (pintype "passive"))
    )
    (net (code "40") (name "/MIPI_D2_N") (class "Default")
      (node (ref "J1") (pin "12") (pinfunction "12_12") (pintype "passive"))
      (node (ref "R27") (pin "1") (pinfunction "1_1") (pintype "passive"))
      (node (ref "U4") (pin "42") (pinfunction "IOT20B/GCLKC_1/BANK1_42") (pintype "passive"))
    )
    (net (code "41") (name "/MIPI_D2_P") (class "Default")
      (node (ref "J1") (pin "11") (pinfunction "11_11") (pintype "passive"))
      (node (ref "R27") (pin "2") (pinfunction "2_2") (pintype "passive"))
      (node (ref "U4") (pin "41") (pinfunction "IOT20A/GCLKT_1/X16/BANK1_41") (pintype "passive"))
    )
    (net (code "42") (name "/MIPI_D3_N") (class "Default")
      (node (ref "J1") (pin "9") (pinfunction "9_9") (pintype "passive"))
      (node (ref "R28") (pin "1") (pinfunction "1_1") (pintype "passive"))
      (node (ref "U4") (pin "40") (pinfunction "IOT26B/BANK1_40") (pintype "passive"))
    )
    (net (code "43") (name "/MIPI_D3_P") (class "Default")
      (node (ref "J1") (pin "8") (pinfunction "8_8") (pintype "passive"))
      (node (ref "R28") (pin "2") (pinfunction "2_2") (pintype "passive"))
      (node (ref "U4") (pin "39") (pinfunction "IOT26A/X16/BANK1_39") (pintype "passive"))
    )
    (net (code "44") (name "/SYS_CLK") (class "Default")
      (node (ref "R30") (pin "1") (pinfunction "1_1") (pintype "passive"))
      (node (ref "U4") (pin "35") (pinfunction "IOR2A/RPLL_T_in/LVDS/X16/BANK2_35") (pintype "passive"))
    )
    (net (code "45") (name "/TPS_PWRUP") (class "Default")
      (node (ref "R11") (pin "1") (pinfunction "1_1") (pintype "passive"))
      (node (ref "U1") (pin "21") (pinfunction "PWRUP_21") (pintype "passive"))
      (node (ref "U5") (pin "16") (pinfunction "B4_16") (pintype "passive"))
    )
    (net (code "46") (name "/TPS_PWRUP_F") (class "Default")
      (node (ref "U4") (pin "17") (pinfunction "IOB6B/BANK3_17") (pintype "passive"))
      (node (ref "U5") (pin "5") (pinfunction "A4_5") (pintype "passive"))
    )
    (net (code "47") (name "/TPS_SCL") (class "Default")
      (node (ref "R5") (pin "1") (pinfunction "1_1") (pintype "passive"))
      (node (ref "U1") (pin "17") (pinfunction "SCL_17") (pintype "passive"))
      (node (ref "U5") (pin "17") (pinfunction "B3_17") (pintype "passive"))
    )
    (net (code "48") (name "/TPS_SCL_F") (class "Default")
      (node (ref "R35") (pin "1") (pinfunction "1_1") (pintype "passive"))
      (node (ref "U4") (pin "18") (pinfunction "IOB13A/BANK3_18") (pintype "passive"))
      (node (ref "U5") (pin "4") (pinfunction "A3_4") (pintype "passive"))
    )
    (net (code "49") (name "/TPS_SDA") (class "Default")
      (node (ref "R8") (pin "1") (pinfunction "1_1") (pintype "passive"))
      (node (ref "U1") (pin "18") (pinfunction "SDA_18") (pintype "passive"))
      (node (ref "U5") (pin "18") (pinfunction "B2_18") (pintype "passive"))
    )
    (net (code "50") (name "/TPS_SDA_F") (class "Default")
      (node (ref "R36") (pin "1") (pinfunction "1_1") (pintype "passive"))
      (node (ref "U4") (pin "19") (pinfunction "IOB13B/BANK3_19") (pintype "passive"))
      (node (ref "U5") (pin "3") (pinfunction "A2_3") (pintype "passive"))
    )
    (net (code "51") (name "GND") (class "Default")
      (node (ref "C1") (pin "1") (pinfunction "1_1") (pintype "passive"))
      (node (ref "C10") (pin "2") (pinfunction "2_2") (pintype "passive"))
      (node (ref "C12") (pin "1") (pinfunction "1_1") (pintype "passive"))
      (node (ref "C13") (pin "2") (pinfunction "2_2") (pintype "passive"))
      (node (ref "C14") (pin "1") (pinfunction "1_1") (pintype "passive"))
      (node (ref "C15") (pin "2") (pinfunction "2_2") (pintype "passive"))
      (node (ref "C17") (pin "1") (pinfunction "1_1") (pintype "passive"))
      (node (ref "C18") (pin "1") (pinfunction "1_1") (pintype "passive"))
      (node (ref "C19") (pin "1") (pinfunction "1_1") (pintype "passive"))
      (node (ref "C2") (pin "1") (pinfunction "1_1") (pintype "passive"))
      (node (ref "C20") (pin "2") (pinfunction "2_2") (pintype "passive"))
      (node (ref "C21") (pin "1") (pinfunction "1_1") (pintype "passive"))
      (node (ref "C22") (pin "1") (pinfunction "1_1") (pintype "passive"))
      (node (ref "C24") (pin "1") (pinfunction "1_1") (pintype "passive"))
      (node (ref "C25") (pin "1") (pinfunction "1_1") (pintype "passive"))
      (node (ref "C26") (pin "1") (pinfunction "1_1") (pintype "passive"))
      (node (ref "C27") (pin "1") (pinfunction "1_1") (pintype "passive"))
      (node (ref "C28") (pin "1") (pinfunction "1_1") (pintype "passive"))
      (node (ref "C3") (pin "1") (pinfunction "1_1") (pintype "passive"))
      (node (ref "C30") (pin "1") (pinfunction "1_1") (pintype "passive"))
      (node (ref "C32") (pin "2") (pinfunction "2_2") (pintype "passive"))
      (node (ref "C33") (pin "2") (pinfunction "2_2") (pintype "passive"))
      (node (ref "C34") (pin "1") (pinfunction "1_1") (pintype "passive"))
      (node (ref "C35") (pin "2") (pinfunction "2_2") (pintype "passive"))
      (node (ref "C36") (pin "1") (pinfunction "1_1") (pintype "passive"))
      (node (ref "C37") (pin "1") (pinfunction "1_1") (pintype "passive"))
      (node (ref "C38") (pin "1") (pinfunction "1_1") (pintype "passive"))
      (node (ref "C39") (pin "1") (pinfunction "1_1") (pintype "passive"))
      (node (ref "C4") (pin "2") (pinfunction "2_2") (pintype "passive"))
      (node (ref "C40") (pin "1") (pinfunction "1_1") (pintype "passive"))
      (node (ref "C41") (pin "1") (pinfunction "1_1") (pintype "passive"))
      (node (ref "C42") (pin "2") (pinfunction "2_2") (pintype "passive"))
      (node (ref "C43") (pin "2") (pinfunction "2_2") (pintype "passive"))
      (node (ref "C44") (pin "1") (pinfunction "1_1") (pintype "passive"))
      (node (ref "C45") (pin "1") (pinfunction "1_1") (pintype "passive"))
      (node (ref "C5") (pin "2") (pinfunction "2_2") (pintype "passive"))
      (node (ref "C6") (pin "1") (pinfunction "1_1") (pintype "passive"))
      (node (ref "C7") (pin "2") (pinfunction "2_2") (pintype "passive"))
      (node (ref "C8") (pin "1") (pinfunction "1_1") (pintype "passive"))
      (node (ref "C9") (pin "2") (pinfunction "2_2") (pintype "passive"))
      (node (ref "J1") (pin "10") (pinfunction "10_10") (pintype "passive"))
      (node (ref "J1") (pin "13") (pinfunction "13_13") (pintype "passive"))
      (node (ref "J1") (pin "16") (pinfunction "16_16") (pintype "passive"))
      (node (ref "J1") (pin "19") (pinfunction "19_19") (pintype "passive"))
      (node (ref "J1") (pin "22") (pinfunction "22_22") (pintype "passive"))
      (node (ref "J1") (pin "23") (pinfunction "23_23") (pintype "passive"))
      (node (ref "J1") (pin "24") (pinfunction "24_24") (pintype "passive"))
      (node (ref "J1") (pin "4") (pinfunction "4_4") (pintype "passive"))
      (node (ref "J1") (pin "7") (pinfunction "7_7") (pintype "passive"))
      (node (ref "J2") (pin "12") (pinfunction "VSS_12") (pintype "passive"))
      (node (ref "J2") (pin "22") (pinfunction "VSS_22") (pintype "passive"))
      (node (ref "J2") (pin "41") (pinfunction "GND_41") (pintype "passive"))
      (node (ref "J2") (pin "42") (pinfunction "GND_42") (pintype "passive"))
      (node (ref "J2") (pin "9") (pinfunction "VSS_9") (pintype "passive"))
      (node (ref "J3") (pin "12") (pinfunction "12_12") (pintype "passive"))
      (node (ref "J3") (pin "2") (pinfunction "2_2") (pintype "passive"))
      (node (ref "J3") (pin "3") (pinfunction "3_3") (pintype "passive"))
      (node (ref "J3") (pin "4") (pinfunction "4_4") (pintype "passive"))
      (node (ref "J3") (pin "6") (pinfunction "6_6") (pintype "passive"))
      (node (ref "J3") (pin "9") (pinfunction "9_9") (pintype "passive"))
      (node (ref "L2") (pin "2") (pinfunction "2_2") (pintype "passive"))
      (node (ref "R11") (pin "2") (pinfunction "2_2") (pintype "passive"))
      (node (ref "R12") (pin "2") (pinfunction "2_2") (pintype "passive"))
      (node (ref "R13") (pin "1") (pinfunction "1_1") (pintype "passive"))
      (node (ref "R16") (pin "2") (pinfunction "2_2") (pintype "passive"))
      (node (ref "R2") (pin "1") (pinfunction "1_1") (pintype "passive"))
      (node (ref "R20") (pin "2") (pinfunction "2_2") (pintype "passive"))
      (node (ref "R25") (pin "2") (pinfunction "2_2") (pintype "passive"))
      (node (ref "R29") (pin "2") (pinfunction "2_2") (pintype "passive"))
      (node (ref "R3") (pin "2") (pinfunction "2_2") (pintype "passive"))
      (node (ref "R4") (pin "2") (pinfunction "2_2") (pintype "passive"))
      (node (ref "R7") (pin "1") (pinfunction "1_1") (pintype "passive"))
      (node (ref "U1") (pin "14") (pinfunction "VCOM_DIS_14") (pintype "passive"))
      (node (ref "U1") (pin "32") (pinfunction "PGND2_32") (pintype "passive"))
      (node (ref "U1") (pin "41") (pinfunction "PGND1_41") (pintype "passive"))
      (node (ref "U1") (pin "48") (pinfunction "AGND2_48") (pintype "passive"))
      (node (ref "U1") (pin "6") (pinfunction "DGND_6") (pintype "passive"))
      (node (ref "U1") (pin "8") (pinfunction "AGND1_8") (pintype "passive"))
      (node (ref "U2") (pin "1") (pinfunction "GND_1") (pintype "passive"))
      (node (ref "U3") (pin "1") (pinfunction "GND3_1") (pintype "passive"))
      (node (ref "U3") (pin "12") (pinfunction "GND1_12") (pintype "passive"))
      (node (ref "U3") (pin "13") (pinfunction "GND1_13") (pintype "passive"))
      (node (ref "U3") (pin "15") (pinfunction "AGND_15") (pintype "passive"))
      (node (ref "U3") (pin "17") (pinfunction "AGND_17") (pintype "passive"))
      (node (ref "U3") (pin "21") (pinfunction "AGND_21") (pintype "passive"))
      (node (ref "U3") (pin "4") (pinfunction "GND2_4") (pintype "passive"))
      (node (ref "U3") (pin "5") (pinfunction "GND2_5") (pintype "passive"))
      (node (ref "U4") (pin "26") (pinfunction "VSS_26") (pintype "passive"))
      (node (ref "U4") (pin "49") (pinfunction "MID_PAD_49") (pintype "passive"))
      (node (ref "U5") (pin "11") (pinfunction "GND_11") (pintype "passive"))
      (node (ref "U5") (pin "21") (pinfunction "EP_21") (pintype "passive"))
      (node (ref "U6") (pin "15") (pinfunction "EP_15") (pintype "passive"))
      (node (ref "U6") (pin "7") (pinfunction "GND_7") (pintype "passive"))
      (node (ref "USB1") (pin "1") (pinfunction "SH1_1") (pintype "passive"))
      (node (ref "USB1") (pin "2") (pinfunction "SH2_2") (pintype "passive"))
      (node (ref "USB1") (pin "3") (pinfunction "SH3_3") (pintype "passive"))
      (node (ref "USB1") (pin "4") (pinfunction "SH4_4") (pintype "passive"))
      (node (ref "USB1") (pin "A1") (pinfunction "GND_A1") (pintype "passive"))
      (node (ref "USB1") (pin "A12") (pinfunction "GND_A12") (pintype "passive"))
      (node (ref "USB1") (pin "B1") (pinfunction "GND_B1") (pintype "passive"))
      (node (ref "USB1") (pin "B12") (pinfunction "GND_B12") (pintype "passive"))
      (node (ref "X1") (pin "2") (pinfunction "GND_2") (pintype "passive"))
    )
    (net (code "52") (name "Net-(C11-Pad2)") (class "Default")
      (node (ref "C11") (pin "2") (pinfunction "2_2") (pintype "passive"))
      (node (ref "D2") (pin "3") (pinfunction "3_3") (pintype "passive"))
    )
    (net (code "53") (name "Net-(C16-Pad2)") (class "Default")
      (node (ref "C16") (pin "2") (pinfunction "2_2") (pintype "passive"))
      (node (ref "D3") (pin "3") (pinfunction "3_3") (pintype "passive"))
    )
    (net (code "54") (name "Net-(C22-Pad2)") (class "Default")
      (node (ref "C22") (pin "2") (pinfunction "2_2") (pintype "passive"))
      (node (ref "C23") (pin "2") (pinfunction "2_2") (pintype "passive"))
      (node (ref "FB2") (pin "2") (pinfunction "2_2") (pintype "passive"))
      (node (ref "L3") (pin "1") (pinfunction "1_1") (pintype "passive"))
      (node (ref "R15") (pin "2") (pinfunction "2_2") (pintype "passive"))
    )
    (net (code "55") (name "Net-(C28-Pad2)") (class "Default")
      (node (ref "C28") (pin "2") (pinfunction "2_2") (pintype "passive"))
      (node (ref "C29") (pin "2") (pinfunction "2_2") (pintype "passive"))
      (node (ref "FB3") (pin "2") (pinfunction "2_2") (pintype "passive"))
      (node (ref "L4") (pin "1") (pinfunction "1_1") (pintype "passive"))
      (node (ref "R17") (pin "2") (pinfunction "2_2") (pintype "passive"))
    )
    (net (code "56") (name "Net-(C30-Pad2)") (class "Default")
      (node (ref "C30") (pin "2") (pinfunction "2_2") (pintype "passive"))
      (node (ref "C31") (pin "2") (pinfunction "2_2") (pintype "passive"))
      (node (ref "FB4") (pin "2") (pinfunction "2_2") (pintype "passive"))
      (node (ref "L5") (pin "1") (pinfunction "1_1") (pintype "passive"))
      (node (ref "R22") (pin "2") (pinfunction "2_2") (pintype "passive"))
    )
    (net (code "57") (name "Net-(C45-Pad2)") (class "Default")
      (node (ref "C45") (pin "2") (pinfunction "2_2") (pintype "passive"))
      (node (ref "R10") (pin "1") (pinfunction "1_1") (pintype "passive"))
      (node (ref "R39") (pin "2") (pinfunction "2_2") (pintype "passive"))
    )
    (net (code "58") (name "Net-(J2-BRD)") (class "Default")
      (node (ref "J2") (pin "40") (pinfunction "BRD_40") (pintype "passive"))
      (node (ref "R31") (pin "2") (pinfunction "2_2") (pintype "passive"))
    )
    (net (code "59") (name "Net-(J2-MODE)") (class "Default")
      (node (ref "J2") (pin "6") (pinfunction "MODE_6") (pintype "passive"))
      (node (ref "R32") (pin "2") (pinfunction "2_2") (pintype "passive"))
    )
    (net (code "60") (name "Net-(J2-XOE)") (class "Default")
      (node (ref "J2") (pin "33") (pinfunction "XOE_33") (pintype "passive"))
      (node (ref "R33") (pin "2") (pinfunction "2_2") (pintype "passive"))
    )
    (net (code "61") (name "Net-(U1-INT#)") (class "Default")
      (node (ref "R1") (pin "1") (pinfunction "1_1") (pintype "passive"))
      (node (ref "U1") (pin "2") (pinfunction "INT#_2") (pintype "passive"))
    )
    (net (code "62") (name "Net-(U1-INT_LDO)") (class "Default")
      (node (ref "C6") (pin "2") (pinfunction "2_2") (pintype "passive"))
      (node (ref "U1") (pin "7") (pinfunction "INT_LDO_7") (pintype "passive"))
    )
    (net (code "63") (name "Net-(U1-TS)") (class "Default")
      (node (ref "R2") (pin "2") (pinfunction "2_2") (pintype "passive"))
      (node (ref "R38") (pin "2") (pinfunction "2_2") (pintype "passive"))
      (node (ref "U1") (pin "47") (pinfunction "TS_47") (pintype "passive"))
    )
    (net (code "64") (name "Net-(U1-VB_SW)") (class "Default")
      (node (ref "D1") (pin "2") (pinfunction "2_2") (pintype "passive"))
      (node (ref "L1") (pin "1") (pinfunction "1_1") (pintype "passive"))
      (node (ref "U1") (pin "40") (pinfunction "VB_SW_40") (pintype "passive"))
    )
    (net (code "65") (name "Net-(U1-VDDH_D)") (class "Default")
      (node (ref "C13") (pin "1") (pinfunction "1_1") (pintype "passive"))
      (node (ref "D2") (pin "1") (pinfunction "1_1") (pintype "passive"))
      (node (ref "U1") (pin "34") (pinfunction "VDDH_D_34") (pintype "passive"))
    )
    (net (code "66") (name "Net-(U1-VDDH_DRV)") (class "Default")
      (node (ref "C11") (pin "1") (pinfunction "1_1") (pintype "passive"))
      (node (ref "U1") (pin "36") (pinfunction "VDDH_DRV_36") (pintype "passive"))
    )
    (net (code "67") (name "Net-(U1-VDDH_FB)") (class "Default")
      (node (ref "R6") (pin "1") (pinfunction "1_1") (pintype "passive"))
      (node (ref "R7") (pin "2") (pinfunction "2_2") (pintype "passive"))
      (node (ref "U1") (pin "33") (pinfunction "VDDH_FB_33") (pintype "passive"))
    )
    (net (code "68") (name "Net-(U1-VEE_D)") (class "Default")
      (node (ref "C15") (pin "1") (pinfunction "1_1") (pintype "passive"))
      (node (ref "D3") (pin "2") (pinfunction "2_2") (pintype "passive"))
      (node (ref "U1") (pin "30") (pinfunction "VEE_D_30") (pintype "passive"))
    )
    (net (code "69") (name "Net-(U1-VEE_DRV)") (class "Default")
      (node (ref "C16") (pin "1") (pinfunction "1_1") (pintype "passive"))
      (node (ref "U1") (pin "28") (pinfunction "VEE_DRV_28") (pintype "passive"))
    )
    (net (code "70") (name "Net-(U1-VEE_FB)") (class "Default")
      (node (ref "R10") (pin "2") (pinfunction "2_2") (pintype "passive"))
      (node (ref "R9") (pin "1") (pinfunction "1_1") (pintype "passive"))
      (node (ref "U1") (pin "31") (pinfunction "VEE_FB_31") (pintype "passive"))
    )
    (net (code "71") (name "Net-(U1-VN_SW)") (class "Default")
      (node (ref "D4") (pin "1") (pinfunction "1_1") (pintype "passive"))
      (node (ref "L2") (pin "1") (pinfunction "1_1") (pintype "passive"))
      (node (ref "U1") (pin "25") (pinfunction "VN_SW_25") (pintype "passive"))
    )
    (net (code "72") (name "Net-(U2-EN)") (class "Default")
      (node (ref "R14") (pin "1") (pinfunction "1_1") (pintype "passive"))
      (node (ref "U2") (pin "2") (pinfunction "EN_2") (pintype "passive"))
    )
    (net (code "73") (name "Net-(U2-IN)") (class "Default")
      (node (ref "C21") (pin "2") (pinfunction "2_2") (pintype "passive"))
      (node (ref "FB1") (pin "1") (pinfunction "1_1") (pintype "passive"))
      (node (ref "U2") (pin "3") (pinfunction "IN_3") (pintype "passive"))
    )
    (net (code "74") (name "Net-(U3-EN1)") (class "Default")
      (node (ref "R18") (pin "2") (pinfunction "2_2") (pintype "passive"))
      (node (ref "U3") (pin "9") (pinfunction "EN1_9") (pintype "passive"))
    )
    (net (code "75") (name "Net-(U3-EN2)") (class "Default")
      (node (ref "R19") (pin "2") (pinfunction "2_2") (pintype "passive"))
      (node (ref "U3") (pin "8") (pinfunction "EN2_8") (pintype "passive"))
    )
    (net (code "76") (name "Net-(U3-EN3)") (class "Default")
      (node (ref "R21") (pin "2") (pinfunction "2_2") (pintype "passive"))
      (node (ref "U3") (pin "18") (pinfunction "EN3_18") (pintype "passive"))
    )
    (net (code "77") (name "Net-(U3-FB1)") (class "Default")
      (node (ref "C23") (pin "1") (pinfunction "1_1") (pintype "passive"))
      (node (ref "R15") (pin "1") (pinfunction "1_1") (pintype "passive"))
      (node (ref "R16") (pin "1") (pinfunction "1_1") (pintype "passive"))
      (node (ref "U3") (pin "14") (pinfunction "FB1_14") (pintype "passive"))
    )
    (net (code "78") (name "Net-(U3-FB2)") (class "Default")
      (node (ref "C29") (pin "1") (pinfunction "1_1") (pintype "passive"))
      (node (ref "R17") (pin "1") (pinfunction "1_1") (pintype "passive"))
      (node (ref "R20") (pin "1") (pinfunction "1_1") (pintype "passive"))
      (node (ref "U3") (pin "3") (pinfunction "FB2_3") (pintype "passive"))
    )
    (net (code "79") (name "Net-(U3-FB3)") (class "Default")
      (node (ref "C31") (pin "1") (pinfunction "1_1") (pintype "passive"))
      (node (ref "R22") (pin "1") (pinfunction "1_1") (pintype "passive"))
      (node (ref "R25") (pin "1") (pinfunction "1_1") (pintype "passive"))
      (node (ref "U3") (pin "2") (pinfunction "FB3_2") (pintype "passive"))
    )
    (net (code "80") (name "Net-(U3-LX1)") (class "Default")
      (node (ref "L3") (pin "2") (pinfunction "2_2") (pintype "passive"))
      (node (ref "U3") (pin "11") (pinfunction "LX1_11") (pintype "passive"))
    )
    (net (code "81") (name "Net-(U3-LX2)") (class "Default")
      (node (ref "L4") (pin "2") (pinfunction "2_2") (pintype "passive"))
      (node (ref "U3") (pin "6") (pinfunction "LX2_6") (pintype "passive"))
    )
    (net (code "82") (name "Net-(U3-LX3)") (class "Default")
      (node (ref "L5") (pin "2") (pinfunction "2_2") (pintype "passive"))
      (node (ref "U3") (pin "20") (pinfunction "LX3_20") (pintype "passive"))
    )
    (net (code "83") (name "Net-(U5-OE)") (class "Default")
      (node (ref "R34") (pin "1") (pinfunction "1_1") (pintype "passive"))
      (node (ref "U5") (pin "10") (pinfunction "OE_10") (pintype "passive"))
    )
    (net (code "84") (name "Net-(U6-OE)") (class "Default")
      (node (ref "R37") (pin "1") (pinfunction "1_1") (pintype "passive"))
      (node (ref "U6") (pin "8") (pinfunction "OE_8") (pintype "passive"))
    )
    (net (code "85") (name "Net-(USB1-CC1)") (class "Default")
      (node (ref "R12") (pin "1") (pinfunction "1_1") (pintype "passive"))
      (node (ref "USB1") (pin "A5") (pinfunction "CC1_A5") (pintype "passive"))
    )
    (net (code "86") (name "Net-(USB1-CC2)") (class "Default")
      (node (ref "R13") (pin "2") (pinfunction "2_2") (pintype "passive"))
      (node (ref "USB1") (pin "B5") (pinfunction "CC2_B5") (pintype "passive"))
    )
    (net (code "87") (name "Net-(X1-IN)") (class "Default")
      (node (ref "C33") (pin "1") (pinfunction "1_1") (pintype "passive"))
      (node (ref "FB5") (pin "1") (pinfunction "1_1") (pintype "passive"))
      (node (ref "X1") (pin "1") (pinfunction "IN_1") (pintype "passive"))
      (node (ref "X1") (pin "4") (pinfunction "VCC_4") (pintype "passive"))
    )
    (net (code "88") (name "Net-(X1-OUT)") (class "Default")
      (node (ref "R30") (pin "2") (pinfunction "2_2") (pintype "passive"))
      (node (ref "X1") (pin "3") (pinfunction "OUT_3") (pintype "passive"))
    )
    (net (code "89") (name "VBUS") (class "Default")
      (node (ref "FB1") (pin "2") (pinfunction "2_2") (pintype "passive"))
      (node (ref "J3") (pin "5") (pinfunction "5_5") (pintype "passive"))
      (node (ref "R14") (pin "2") (pinfunction "2_2") (pintype "passive"))
      (node (ref "USB1") (pin "A4") (pinfunction "VBUS_A4") (pintype "passive"))
      (node (ref "USB1") (pin "A9") (pinfunction "VBUS_A9") (pintype "passive"))
      (node (ref "USB1") (pin "B4") (pinfunction "VBUS_B4") (pintype "passive"))
      (node (ref "USB1") (pin "B9") (pinfunction "VBUS_B9") (pintype "passive"))
    )
    (net (code "90") (name "VB_OUT") (class "Default")
      (node (ref "C7") (pin "1") (pinfunction "1_1") (pintype "passive"))
      (node (ref "C9") (pin "1") (pinfunction "1_1") (pintype "passive"))
      (node (ref "D1") (pin "1") (pinfunction "1_1") (pintype "passive"))
      (node (ref "U1") (pin "37") (pinfunction "VDDH_IN_37") (pintype "passive"))
      (node (ref "U1") (pin "42") (pinfunction "VB_42") (pintype "passive"))
      (node (ref "U1") (pin "43") (pinfunction "VPOS_IN_43") (pintype "passive"))
    )
    (net (code "91") (name "VCC_1V2") (class "Default")
      (node (ref "C36") (pin "2") (pinfunction "2_2") (pintype "passive"))
      (node (ref "C38") (pin "2") (pinfunction "2_2") (pintype "passive"))
      (node (ref "C39") (pin "2") (pinfunction "2_2") (pintype "passive"))
      (node (ref "FB3") (pin "1") (pinfunction "1_1") (pintype "passive"))
      (node (ref "U4") (pin "11") (pinfunction "VCC_11") (pintype "passive"))
      (node (ref "U4") (pin "37") (pinfunction "VCC_37") (pintype "passive"))
      (node (ref "U4") (pin "38") (pinfunction "VCCO1_38") (pintype "passive"))
    )
    (net (code "92") (name "VCC_1V8") (class "Default")
      (node (ref "C37") (pin "2") (pinfunction "2_2") (pintype "passive"))
      (node (ref "C40") (pin "2") (pinfunction "2_2") (pintype "passive"))
      (node (ref "C42") (pin "1") (pinfunction "1_1") (pintype "passive"))
      (node (ref "C43") (pin "1") (pinfunction "1_1") (pintype "passive"))
      (node (ref "FB4") (pin "1") (pinfunction "1_1") (pintype "passive"))
      (node (ref "R34") (pin "2") (pinfunction "2_2") (pintype "passive"))
      (node (ref "R35") (pin "2") (pinfunction "2_2") (pintype "passive"))
      (node (ref "R36") (pin "2") (pinfunction "2_2") (pintype "passive"))
      (node (ref "R37") (pin "2") (pinfunction "2_2") (pintype "passive"))
      (node (ref "U4") (pin "12") (pinfunction "VCCO3_12") (pintype "passive"))
      (node (ref "U4") (pin "24") (pinfunction "VCCO3_24") (pintype "passive"))
      (node (ref "U5") (pin "2") (pinfunction "VCCA_2") (pintype "passive"))
      (node (ref "U6") (pin "1") (pinfunction "VA_1") (pintype "passive"))
    )
    (net (code "93") (name "VCC_3V3") (class "Default")
      (node (ref "C32") (pin "1") (pinfunction "1_1") (pintype "passive"))
      (node (ref "C34") (pin "2") (pinfunction "2_2") (pintype "passive"))
      (node (ref "C35") (pin "1") (pinfunction "1_1") (pintype "passive"))
      (node (ref "C41") (pin "2") (pinfunction "2_2") (pintype "passive"))
      (node (ref "C44") (pin "2") (pinfunction "2_2") (pintype "passive"))
      (node (ref "FB2") (pin "1") (pinfunction "1_1") (pintype "passive"))
      (node (ref "FB5") (pin "2") (pinfunction "2_2") (pintype "passive"))
      (node (ref "J2") (pin "11") (pinfunction "VDD_11") (pintype "passive"))
      (node (ref "J2") (pin "34") (pinfunction "VDD_34") (pintype "passive"))
      (node (ref "J2") (pin "5") (pinfunction "VDD_5") (pintype "passive"))
      (node (ref "J3") (pin "1") (pinfunction "1_1") (pintype "passive"))
      (node (ref "R1") (pin "2") (pinfunction "2_2") (pintype "passive"))
      (node (ref "R3") (pin "1") (pinfunction "1_1") (pintype "passive"))
      (node (ref "R32") (pin "1") (pinfunction "1_1") (pintype "passive"))
      (node (ref "R33") (pin "1") (pinfunction "1_1") (pintype "passive"))
      (node (ref "R4") (pin "1") (pinfunction "1_1") (pintype "passive"))
      (node (ref "R5") (pin "2") (pinfunction "2_2") (pintype "passive"))
      (node (ref "R8") (pin "2") (pinfunction "2_2") (pintype "passive"))
      (node (ref "U1") (pin "12") (pinfunction "VCOM_CTRL_12") (pintype "passive"))
      (node (ref "U1") (pin "5") (pinfunction "WAKEUP_5") (pintype "passive"))
      (node (ref "U4") (pin "25") (pinfunction "VCCX_25") (pintype "passive"))
      (node (ref "U4") (pin "36") (pinfunction "VCCO2_36") (pintype "passive"))
      (node (ref "U4") (pin "5") (pinfunction "VCCO0_5") (pintype "passive"))
      (node (ref "U5") (pin "19") (pinfunction "VCCB_19") (pintype "passive"))
      (node (ref "U6") (pin "14") (pinfunction "VB_14") (pintype "passive"))
    )
    (net (code "94") (name "VCOM") (class "Default")
      (node (ref "C12") (pin "2") (pinfunction "2_2") (pintype "passive"))
      (node (ref "J2") (pin "10") (pinfunction "VCOM_10") (pintype "passive"))
      (node (ref "R31") (pin "1") (pinfunction "1_1") (pintype "passive"))
      (node (ref "U1") (pin "15") (pinfunction "VCOM_15") (pintype "passive"))
    )
    (net (code "95") (name "VGH") (class "Default")
      (node (ref "C10") (pin "1") (pinfunction "1_1") (pintype "passive"))
      (node (ref "D2") (pin "2") (pinfunction "2_2") (pintype "passive"))
      (node (ref "J2") (pin "3") (pinfunction "VGH_3") (pintype "passive"))
      (node (ref "R6") (pin "2") (pinfunction "2_2") (pintype "passive"))
      (node (ref "U1") (pin "35") (pinfunction "VDDH_DIS_35") (pintype "passive"))
    )
    (net (code "96") (name "VGL") (class "Default")
      (node (ref "C19") (pin "2") (pinfunction "2_2") (pintype "passive"))
      (node (ref "D3") (pin "1") (pinfunction "1_1") (pintype "passive"))
      (node (ref "J2") (pin "1") (pinfunction "VGL_1") (pintype "passive"))
      (node (ref "R9") (pin "2") (pinfunction "2_2") (pintype "passive"))
      (node (ref "U1") (pin "29") (pinfunction "VEE_DIS_29") (pintype "passive"))
    )
    (net (code "97") (name "VIN") (class "Default")
      (node (ref "C17") (pin "2") (pinfunction "2_2") (pintype "passive"))
      (node (ref "C20") (pin "1") (pinfunction "1_1") (pintype "passive"))
      (node (ref "C24") (pin "2") (pinfunction "2_2") (pintype "passive"))
      (node (ref "C25") (pin "2") (pinfunction "2_2") (pintype "passive"))
      (node (ref "C26") (pin "2") (pinfunction "2_2") (pintype "passive"))
      (node (ref "C27") (pin "2") (pinfunction "2_2") (pintype "passive"))
      (node (ref "C5") (pin "1") (pinfunction "1_1") (pintype "passive"))
      (node (ref "C8") (pin "2") (pinfunction "2_2") (pintype "passive"))
      (node (ref "L1") (pin "2") (pinfunction "2_2") (pintype "passive"))
      (node (ref "R18") (pin "1") (pinfunction "1_1") (pintype "passive"))
      (node (ref "R19") (pin "1") (pinfunction "1_1") (pintype "passive"))
      (node (ref "R21") (pin "1") (pinfunction "1_1") (pintype "passive"))
      (node (ref "U1") (pin "10") (pinfunction "VIN_10") (pintype "passive"))
      (node (ref "U1") (pin "24") (pinfunction "VIN_P_24") (pintype "passive"))
      (node (ref "U2") (pin "4") (pinfunction "OUT_4") (pintype "passive"))
      (node (ref "U3") (pin "10") (pinfunction "VIN1_10") (pintype "passive"))
      (node (ref "U3") (pin "16") (pinfunction "VCC_16") (pintype "passive"))
      (node (ref "U3") (pin "19") (pinfunction "VIN3_19") (pintype "passive"))
      (node (ref "U3") (pin "7") (pinfunction "VIN2_7") (pintype "passive"))
    )
    (net (code "98") (name "VNEG") (class "Default")
      (node (ref "C2") (pin "2") (pinfunction "2_2") (pintype "passive"))
      (node (ref "J2") (pin "38") (pinfunction "VNEG_38") (pintype "passive"))
      (node (ref "U1") (pin "3") (pinfunction "VNEG_3") (pintype "passive"))
      (node (ref "U1") (pin "9") (pinfunction "VNEG_DIS_9") (pintype "passive"))
    )
    (net (code "99") (name "VN_OUT") (class "Default")
      (node (ref "C14") (pin "2") (pinfunction "2_2") (pintype "passive"))
      (node (ref "C18") (pin "2") (pinfunction "2_2") (pintype "passive"))
      (node (ref "C3") (pin "2") (pinfunction "2_2") (pintype "passive"))
      (node (ref "D4") (pin "2") (pinfunction "2_2") (pintype "passive"))
      (node (ref "U1") (pin "16") (pinfunction "VCOM_PWR_16") (pintype "passive"))
      (node (ref "U1") (pin "22") (pinfunction "PBKG_22") (pintype "passive"))
      (node (ref "U1") (pin "26") (pinfunction "VN_26") (pintype "passive"))
      (node (ref "U1") (pin "27") (pinfunction "VEE_IN_27") (pintype "passive"))
      (node (ref "U1") (pin "4") (pinfunction "VNEG_IN_4") (pintype "passive"))
      (node (ref "U1") (pin "49") (pinfunction "EP_49") (pintype "passive"))
    )
    (net (code "100") (name "VPOS") (class "Default")
      (node (ref "C4") (pin "1") (pinfunction "1_1") (pintype "passive"))
      (node (ref "J2") (pin "36") (pinfunction "VPOS_36") (pintype "passive"))
      (node (ref "U1") (pin "19") (pinfunction "VPOS_DIS_19") (pintype "passive"))
      (node (ref "U1") (pin "44") (pinfunction "VPOS_44") (pintype "passive"))
    )
    (net (code "101") (name "VREF") (class "Default")
      (node (ref "C1") (pin "2") (pinfunction "2_2") (pintype "passive"))
      (node (ref "R38") (pin "1") (pinfunction "1_1") (pintype "passive"))
      (node (ref "R39") (pin "1") (pinfunction "1_1") (pintype "passive"))
      (node (ref "U1") (pin "1") (pinfunction "VREF_1") (pintype "passive"))
    )
    (net (code "102") (name "unconnected-(J1-Pad1)") (class "Default")
      (node (ref "J1") (pin "1") (pinfunction "1_1") (pintype "passive+no_connect"))
    )
    (net (code "103") (name "unconnected-(J1-Pad2)") (class "Default")
      (node (ref "J1") (pin "2") (pinfunction "2_2") (pintype "passive+no_connect"))
    )
    (net (code "104") (name "unconnected-(J1-Pad3)") (class "Default")
      (node (ref "J1") (pin "3") (pinfunction "3_3") (pintype "passive+no_connect"))
    )
    (net (code "105") (name "unconnected-(J1-Pad5)") (class "Default")
      (node (ref "J1") (pin "5") (pinfunction "5_5") (pintype "passive+no_connect"))
    )
    (net (code "106") (name "unconnected-(J1-Pad6)") (class "Default")
      (node (ref "J1") (pin "6") (pinfunction "6_6") (pintype "passive+no_connect"))
    )
    (net (code "107") (name "unconnected-(J2-NC-Pad2)") (class "Default")
      (node (ref "J2") (pin "2") (pinfunction "NC_2") (pintype "passive+no_connect"))
    )
    (net (code "108") (name "unconnected-(J2-NC-Pad4)") (class "Default")
      (node (ref "J2") (pin "4") (pinfunction "NC_4") (pintype "passive+no_connect"))
    )
    (net (code "109") (name "unconnected-(J2-NC-Pad35)") (class "Default")
      (node (ref "J2") (pin "35") (pinfunction "NC_35") (pintype "passive+no_connect"))
    )
    (net (code "110") (name "unconnected-(J2-NC-Pad37)") (class "Default")
      (node (ref "J2") (pin "37") (pinfunction "NC_37") (pintype "passive+no_connect"))
    )
    (net (code "111") (name "unconnected-(J2-NC-Pad39)") (class "Default")
      (node (ref "J2") (pin "39") (pinfunction "NC_39") (pintype "passive+no_connect"))
    )
    (net (code "112") (name "unconnected-(U1-NC-Pad11)") (class "Default")
      (node (ref "U1") (pin "11") (pinfunction "NC_11") (pintype "passive+no_connect"))
    )
    (net (code "113") (name "unconnected-(U1-NC-Pad13)") (class "Default")
      (node (ref "U1") (pin "13") (pinfunction "NC_13") (pintype "passive+no_connect"))
    )
    (net (code "114") (name "unconnected-(U1-NC-Pad20)") (class "Default")
      (node (ref "U1") (pin "20") (pinfunction "NC_20") (pintype "passive+no_connect"))
    )
    (net (code "115") (name "unconnected-(U1-NC-Pad38)") (class "Default")
      (node (ref "U1") (pin "38") (pinfunction "NC_38") (pintype "passive+no_connect"))
    )
    (net (code "116") (name "unconnected-(U1-NC-Pad39)") (class "Default")
      (node (ref "U1") (pin "39") (pinfunction "NC_39") (pintype "passive+no_connect"))
    )
    (net (code "117") (name "unconnected-(U1-PWR_GOOD-Pad23)") (class "Default")
      (node (ref "U1") (pin "23") (pinfunction "PWR_GOOD_23") (pintype "passive+no_connect"))
    )
    (net (code "118") (name "unconnected-(U1-V3P3-Pad46)") (class "Default")
      (node (ref "U1") (pin "46") (pinfunction "V3P3_46") (pintype "passive+no_connect"))
    )
    (net (code "119") (name "unconnected-(U1-VIN3P3-Pad45)") (class "Default")
      (node (ref "U1") (pin "45") (pinfunction "VIN3P3_45") (pintype "passive+no_connect"))
    )
    (net (code "120") (name "unconnected-(U5-A1-Pad1)") (class "Default")
      (node (ref "U5") (pin "1") (pinfunction "A1_1") (pintype "passive+no_connect"))
    )
    (net (code "121") (name "unconnected-(U5-B1-Pad20)") (class "Default")
      (node (ref "U5") (pin "20") (pinfunction "B1_20") (pintype "passive+no_connect"))
    )
    (net (code "122") (name "unconnected-(U6-NC-Pad6)") (class "Default")
      (node (ref "U6") (pin "6") (pinfunction "NC_6") (pintype "passive+no_connect"))
    )
    (net (code "123") (name "unconnected-(U6-NC-Pad9)") (class "Default")
      (node (ref "U6") (pin "9") (pinfunction "NC_9") (pintype "passive+no_connect"))
    )
    (net (code "124") (name "unconnected-(USB1-D+-PadA6)") (class "Default")
      (node (ref "USB1") (pin "A6") (pinfunction "D+_A6") (pintype "passive+no_connect"))
    )
    (net (code "125") (name "unconnected-(USB1-D+-PadB6)") (class "Default")
      (node (ref "USB1") (pin "B6") (pinfunction "D+_B6") (pintype "passive+no_connect"))
    )
    (net (code "126") (name "unconnected-(USB1-D--PadA7)") (class "Default")
      (node (ref "USB1") (pin "A7") (pinfunction "D-_A7") (pintype "passive+no_connect"))
    )
    (net (code "127") (name "unconnected-(USB1-D--PadB7)") (class "Default")
      (node (ref "USB1") (pin "B7") (pinfunction "D-_B7") (pintype "passive+no_connect"))
    )
  )
)
